# Tubes_board.net
KiCad netlist of a schematic drawn in EAGLE
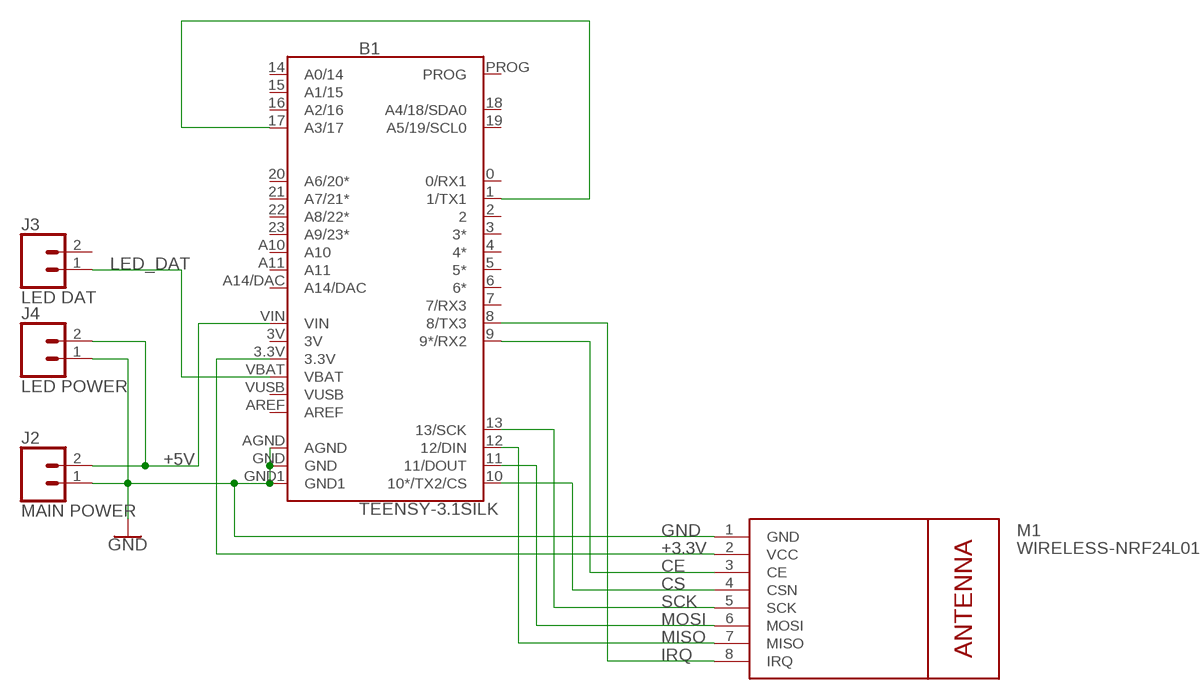
[diagram p0: schematic, sheet 1]

(export (version "E")
  (design (tool "Eeschema 10.0.6"))
  (components
    (comp (ref "B1")
      (value "TEENSY-3.1SILK")
      (footprint "eagle-import:TEENSY-3.1")
      (libsource (lib "eagle-import") (part "TEENSY-3.1SILK"))
    )
    (comp (ref "J2")
      (value "MAIN POWER")
      (footprint "eagle-import:SCREWTERMINAL-5MM-2")
      (libsource (lib "eagle-import") (part "CONN_025MM"))
    )
    (comp (ref "J3")
      (value "LED DAT")
      (footprint "eagle-import:SCREWTERMINAL-5MM-2")
      (libsource (lib "eagle-import") (part "CONN_025MM"))
    )
    (comp (ref "J4")
      (value "LED POWER")
      (footprint "eagle-import:SCREWTERMINAL-5MM-2")
      (libsource (lib "eagle-import") (part "CONN_025MM"))
    )
    (comp (ref "M1")
      (value "WIRELESS-NRF24L01")
      (footprint "eagle-import:WIRELESS-NRF24L01")
      (libsource (lib "eagle-import") (part "WIRELESS-NRF24L01"))
    )
  )
  (nets
    (net (code "1") (name "/+3.3V") (class "Default")
      (node (ref "B1") (pin "3.3V") (pinfunction "3.3V_3.3V") (pintype "power_in"))
      (node (ref "M1") (pin "2") (pinfunction "VCC_2") (pintype "power_in"))
    )
    (net (code "2") (name "/+5V") (class "Default")
      (node (ref "B1") (pin "VIN") (pinfunction "VIN_VIN") (pintype "power_in"))
      (node (ref "J2") (pin "2") (pinfunction "2_2") (pintype "passive"))
      (node (ref "J4") (pin "2") (pinfunction "2_2") (pintype "passive"))
    )
    (net (code "3") (name "/3V") (class "Default")
      (node (ref "B1") (pin "3V") (pinfunction "3V_3V") (pintype "power_in"))
    )
    (net (code "4") (name "/CE") (class "Default")
      (node (ref "B1") (pin "9") (pinfunction "9*/RX2_9") (pintype "bidirectional"))
      (node (ref "M1") (pin "3") (pinfunction "CE_3") (pintype "bidirectional"))
    )
    (net (code "5") (name "/CS") (class "Default")
      (node (ref "B1") (pin "10") (pinfunction "10*/TX2/CS_10") (pintype "bidirectional"))
      (node (ref "M1") (pin "4") (pinfunction "CSN_4") (pintype "bidirectional"))
    )
    (net (code "6") (name "/IRQ") (class "Default")
      (node (ref "B1") (pin "8") (pinfunction "8/TX3_8") (pintype "bidirectional"))
      (node (ref "M1") (pin "8") (pinfunction "IRQ_8") (pintype "bidirectional"))
    )
    (net (code "7") (name "/LED_DAT") (class "Default")
      (node (ref "B1") (pin "VBAT") (pinfunction "VBAT_VBAT") (pintype "power_in"))
      (node (ref "J3") (pin "1") (pinfunction "1_1") (pintype "passive"))
    )
    (net (code "8") (name "/MISO") (class "Default")
      (node (ref "B1") (pin "12") (pinfunction "12/DIN_12") (pintype "bidirectional"))
      (node (ref "M1") (pin "7") (pinfunction "MISO_7") (pintype "bidirectional"))
    )
    (net (code "9") (name "/MOSI") (class "Default")
      (node (ref "B1") (pin "11") (pinfunction "11/DOUT_11") (pintype "bidirectional"))
      (node (ref "M1") (pin "6") (pinfunction "MOSI_6") (pintype "bidirectional"))
    )
    (net (code "10") (name "/SCK") (class "Default")
      (node (ref "B1") (pin "13") (pinfunction "13/SCK_13") (pintype "bidirectional"))
      (node (ref "M1") (pin "5") (pinfunction "SCK_5") (pintype "bidirectional"))
    )
    (net (code "11") (name "/VUSB") (class "Default")
      (node (ref "B1") (pin "VUSB") (pinfunction "VUSB_VUSB") (pintype "power_in"))
    )
    (net (code "12") (name "GND") (class "Default")
      (node (ref "B1") (pin "AGND") (pinfunction "AGND_AGND") (pintype "power_in"))
      (node (ref "B1") (pin "GND") (pinfunction "GND_GND") (pintype "power_in"))
      (node (ref "B1") (pin "GND1") (pinfunction "GND1_GND1") (pintype "power_in"))
      (node (ref "J2") (pin "1") (pinfunction "1_1") (pintype "passive"))
      (node (ref "J4") (pin "1") (pinfunction "1_1") (pintype "passive"))
      (node (ref "M1") (pin "1") (pinfunction "GND_1") (pintype "power_in"))
    )
    (net (code "13") (name "Net-(B1-1{slash}TX1)") (class "Default")
      (node (ref "B1") (pin "1") (pinfunction "1/TX1_1") (pintype "bidirectional"))
      (node (ref "B1") (pin "17") (pinfunction "A3/17_17") (pintype "bidirectional"))
    )
    (net (code "14") (name "unconnected-(B1-0{slash}RX1-Pad0)") (class "Default")
      (node (ref "B1") (pin "0") (pinfunction "0/RX1_0") (pintype "bidirectional"))
    )
    (net (code "15") (name "unconnected-(B1-3*-Pad3)") (class "Default")
      (node (ref "B1") (pin "3") (pinfunction "3*_3") (pintype "bidirectional"))
    )
    (net (code "16") (name "unconnected-(B1-4*-Pad4)") (class "Default")
      (node (ref "B1") (pin "4") (pinfunction "4*_4") (pintype "bidirectional"))
    )
    (net (code "17") (name "unconnected-(B1-5*-Pad5)") (class "Default")
      (node (ref "B1") (pin "5") (pinfunction "5*_5") (pintype "bidirectional"))
    )
    (net (code "18") (name "unconnected-(B1-6*-Pad6)") (class "Default")
      (node (ref "B1") (pin "6") (pinfunction "6*_6") (pintype "bidirectional"))
    )
    (net (code "19") (name "unconnected-(B1-7{slash}RX3-Pad7)") (class "Default")
      (node (ref "B1") (pin "7") (pinfunction "7/RX3_7") (pintype "bidirectional"))
    )
    (net (code "20") (name "unconnected-(B1-A0{slash}14-Pad14)") (class "Default")
      (node (ref "B1") (pin "14") (pinfunction "A0/14_14") (pintype "bidirectional"))
    )
    (net (code "21") (name "unconnected-(B1-A1{slash}15-Pad15)") (class "Default")
      (node (ref "B1") (pin "15") (pinfunction "A1/15_15") (pintype "bidirectional"))
    )
    (net (code "22") (name "unconnected-(B1-A2{slash}16-Pad16)") (class "Default")
      (node (ref "B1") (pin "16") (pinfunction "A2/16_16") (pintype "bidirectional"))
    )
    (net (code "23") (name "unconnected-(B1-A4{slash}18{slash}SDA0-Pad18)") (class "Default")
      (node (ref "B1") (pin "18") (pinfunction "A4/18/SDA0_18") (pintype "bidirectional"))
    )
    (net (code "24") (name "unconnected-(B1-A5{slash}19{slash}SCL0-Pad19)") (class "Default")
      (node (ref "B1") (pin "19") (pinfunction "A5/19/SCL0_19") (pintype "bidirectional"))
    )
    (net (code "25") (name "unconnected-(B1-A6{slash}20*-Pad20)") (class "Default")
      (node (ref "B1") (pin "20") (pinfunction "A6/20*_20") (pintype "bidirectional"))
    )
    (net (code "26") (name "unconnected-(B1-A7{slash}21*-Pad21)") (class "Default")
      (node (ref "B1") (pin "21") (pinfunction "A7/21*_21") (pintype "bidirectional"))
    )
    (net (code "27") (name "unconnected-(B1-A8{slash}22*-Pad22)") (class "Default")
      (node (ref "B1") (pin "22") (pinfunction "A8/22*_22") (pintype "bidirectional"))
    )
    (net (code "28") (name "unconnected-(B1-A9{slash}23*-Pad23)") (class "Default")
      (node (ref "B1") (pin "23") (pinfunction "A9/23*_23") (pintype "bidirectional"))
    )
    (net (code "29") (name "unconnected-(B1-Pad2)") (class "Default")
      (node (ref "B1") (pin "2") (pinfunction "2_2") (pintype "bidirectional"))
    )
    (net (code "30") (name "unconnected-(B1-PadA10)") (class "Default")
      (node (ref "B1") (pin "A10") (pinfunction "A10_A10") (pintype "bidirectional"))
    )
    (net (code "31") (name "unconnected-(B1-PadA11)") (class "Default")
      (node (ref "B1") (pin "A11") (pinfunction "A11_A11") (pintype "bidirectional"))
    )
    (net (code "32") (name "unconnected-(B1-PadA14{slash}DAC)") (class "Default")
      (node (ref "B1") (pin "A14/DAC") (pinfunction "A14/DAC_A14/DAC") (pintype "bidirectional"))
    )
    (net (code "33") (name "unconnected-(B1-PadAREF)") (class "Default")
      (node (ref "B1") (pin "AREF") (pinfunction "AREF_AREF") (pintype "bidirectional"))
    )
    (net (code "34") (name "unconnected-(B1-PadPROG)") (class "Default")
      (node (ref "B1") (pin "PROG") (pinfunction "PROG_PROG") (pintype "bidirectional"))
    )
    (net (code "35") (name "unconnected-(J3-Pad2)") (class "Default")
      (node (ref "J3") (pin "2") (pinfunction "2_2") (pintype "passive"))
    )
  )
)
